# Boost-converter.net
KiCad netlist of a schematic drawn in EAGLE
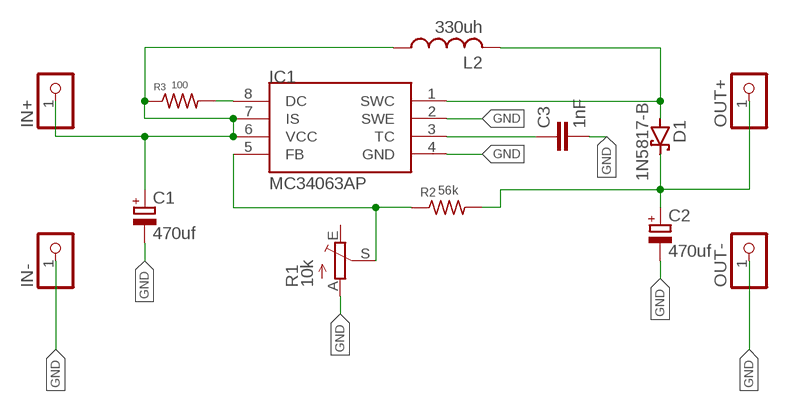
[diagram p0: schematic, sheet 1]

(export (version "E")
  (design (tool "Eeschema 10.0.6"))
  (components
    (comp (ref "C1")
      (value "470uf")
      (footprint "eagle-import:E3,5-8")
      (libsource (lib "eagle-import") (part "CAP_POL"))
    )
    (comp (ref "C2")
      (value "470uf")
      (footprint "eagle-import:E3,5-8")
      (libsource (lib "eagle-import") (part "CAP_POL"))
    )
    (comp (ref "C3")
      (value "1nF")
      (footprint "eagle-import:C025-025X050")
      (libsource (lib "eagle-import") (part "CAPACITOR"))
    )
    (comp (ref "D1")
      (value "1N5817-B")
      (footprint "eagle-import:DO41-7.6")
      (libsource (lib "eagle-import") (part "1N5817-B"))
    )
    (comp (ref "IC1")
      (value "MC34063AP")
      (footprint "eagle-import:DIL08")
      (libsource (lib "eagle-import") (part "MC34063AP"))
    )
    (comp (ref "IN+")
      (value "PINHD-1X1")
      (footprint "eagle-import:1X01")
      (libsource (lib "eagle-import") (part "PINHD-1X1"))
    )
    (comp (ref "IN-")
      (value "PINHD-1X1")
      (footprint "eagle-import:1X01")
      (libsource (lib "eagle-import") (part "PINHD-1X1"))
    )
    (comp (ref "L2")
      (value "330uh")
      (footprint "eagle-import:0207_10")
      (libsource (lib "eagle-import") (part "L-US0207/10"))
    )
    (comp (ref "OUT+")
      (value "PINHD-1X1")
      (footprint "eagle-import:1X01")
      (libsource (lib "eagle-import") (part "PINHD-1X1"))
    )
    (comp (ref "OUT-")
      (value "PINHD-1X1")
      (footprint "eagle-import:1X01")
      (libsource (lib "eagle-import") (part "PINHD-1X1"))
    )
    (comp (ref "R1")
      (value "10k")
      (footprint "eagle-import:CA6V")
      (libsource (lib "eagle-import") (part "TRIM_EU-CA6V"))
    )
    (comp (ref "R2")
      (value "56k")
      (footprint "eagle-import:0204_7")
      (libsource (lib "eagle-import") (part "RES-7"))
    )
    (comp (ref "R3")
      (value "100")
      (footprint "eagle-import:0204_7")
      (libsource (lib "eagle-import") (part "RES-7"))
    )
  )
  (nets
    (net (code "1") (name "GND") (class "Default")
      (node (ref "C1") (pin "-") (pinfunction "-_-") (pintype "passive"))
      (node (ref "C2") (pin "-") (pinfunction "-_-") (pintype "passive"))
      (node (ref "C3") (pin "2") (pinfunction "2_2") (pintype "passive"))
      (node (ref "IC1") (pin "2") (pinfunction "SWE_2") (pintype "passive"))
      (node (ref "IC1") (pin "4") (pinfunction "GND_4") (pintype "passive"))
      (node (ref "IN-") (pin "1") (pinfunction "1_1") (pintype "passive"))
      (node (ref "OUT-") (pin "1") (pinfunction "1_1") (pintype "passive"))
      (node (ref "R1") (pin "A") (pinfunction "A_A") (pintype "passive"))
    )
    (net (code "2") (name "Net-(C2-Pad+)") (class "Default")
      (node (ref "C2") (pin "+") (pinfunction "+_+") (pintype "passive"))
      (node (ref "D1") (pin "C") (pinfunction "C_C") (pintype "passive"))
      (node (ref "OUT+") (pin "1") (pinfunction "1_1") (pintype "passive"))
      (node (ref "R2") (pin "2") (pinfunction "2_2") (pintype "passive"))
    )
    (net (code "3") (name "Net-(IC1-DC)") (class "Default")
      (node (ref "IC1") (pin "8") (pinfunction "DC_8") (pintype "passive"))
      (node (ref "R3") (pin "2") (pinfunction "2_2") (pintype "passive"))
    )
    (net (code "4") (name "Net-(IC1-FB)") (class "Default")
      (node (ref "IC1") (pin "5") (pinfunction "FB_5") (pintype "passive"))
      (node (ref "R1") (pin "S") (pinfunction "S_S") (pintype "passive"))
      (node (ref "R2") (pin "1") (pinfunction "1_1") (pintype "passive"))
    )
    (net (code "5") (name "Net-(IC1-IS)") (class "Default")
      (node (ref "C1") (pin "+") (pinfunction "+_+") (pintype "passive"))
      (node (ref "IC1") (pin "6") (pinfunction "VCC_6") (pintype "passive"))
      (node (ref "IC1") (pin "7") (pinfunction "IS_7") (pintype "passive"))
      (node (ref "IN+") (pin "1") (pinfunction "1_1") (pintype "passive"))
      (node (ref "L2") (pin "1") (pinfunction "1_1") (pintype "passive"))
      (node (ref "R3") (pin "1") (pinfunction "1_1") (pintype "passive"))
    )
    (net (code "6") (name "Net-(IC1-SWC)") (class "Default")
      (node (ref "D1") (pin "A") (pinfunction "A_A") (pintype "passive"))
      (node (ref "IC1") (pin "1") (pinfunction "SWC_1") (pintype "passive"))
      (node (ref "L2") (pin "2") (pinfunction "2_2") (pintype "passive"))
    )
    (net (code "7") (name "Net-(IC1-TC)") (class "Default")
      (node (ref "C3") (pin "1") (pinfunction "1_1") (pintype "passive"))
      (node (ref "IC1") (pin "3") (pinfunction "TC_3") (pintype "passive"))
    )
    (net (code "8") (name "unconnected-(R1-PadE)") (class "Default")
      (node (ref "R1") (pin "E") (pinfunction "E_E") (pintype "passive"))
    )
  )
)
